# 4.net
KiCad netlist of a schematic drawn in Altium Designer
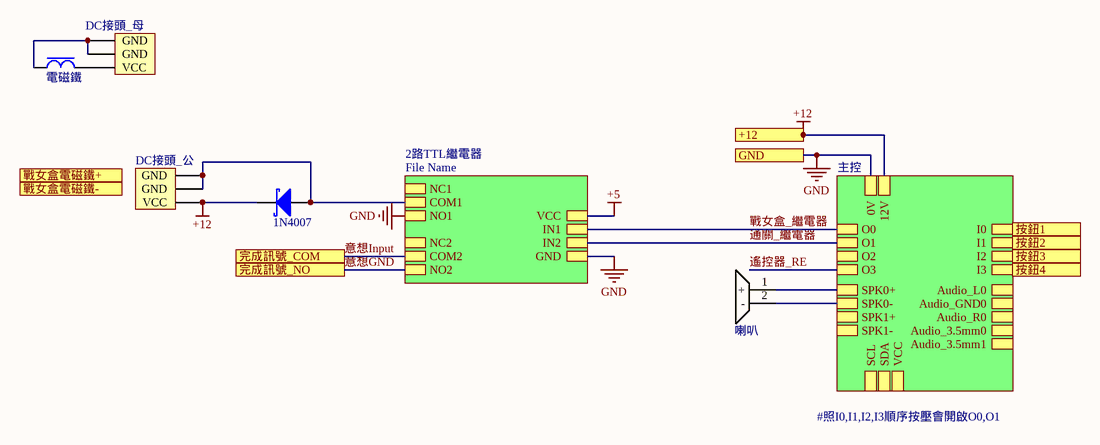
[diagram p0: 松菸_幻影光靈_屍禁_4順序按鈕.SchDoc]

(export (version "E")
  (design (tool "Eeschema 10.0.6"))
  (components
    (comp (ref "B38")
      (value "喇叭")
      (footprint "Buzzer_12085")
      (description "無源蜂鳴器")
      (libsource (lib "MyLibray") (part "Buzzer"))
    )
    (comp (ref "Cn94")
      (value "DC接頭_母")
      (footprint "Connector_DC-005")
      (description "連接器,DC直流接頭")
      (libsource (lib "") (part "Contact_DC_1"))
    )
    (comp (ref "Cn95")
      (value "DC接頭_公")
      (footprint "Connector_DC-005")
      (description "連接器,DC直流接頭")
      (libsource (lib "MyLibray") (part "Contact_DC"))
    )
    (comp (ref "I10")
      (value "電磁鐵")
      (footprint "Inductor-0420")
      (description "一體成型電感")
      (libsource (lib "MyLibray") (part "Inductor"))
    )
    (comp (ref "SD1")
      (value "1N4007")
      (footprint "Diode_SMA")
      (description "二極體_蕭特基")
      (libsource (lib "MyLibray") (part "Diode_Schottky"))
    )
  )
  (nets
    (net (code "2") (name "+12") (class "Default")
      (node (ref "Cn95") (pin "1") (pinfunction "VCC_1") (pintype "passive"))
      (node (ref "SD1") (pin "1") (pinfunction "K_1") (pintype "passive"))
    )
    (net (code "8") (name "/COM1") (class "Default")
      (node (ref "Cn95") (pin "2") (pinfunction "GND_2") (pintype "passive"))
      (node (ref "Cn95") (pin "3") (pinfunction "GND_3") (pintype "passive"))
      (node (ref "SD1") (pin "2") (pinfunction "A_2") (pintype "passive"))
    )
    (net (code "14") (name "/SPK0+") (class "Default")
      (node (ref "B38") (pin "1") (pinfunction "+_1") (pintype "passive"))
    )
    (net (code "15") (name "/SPK0-") (class "Default")
      (node (ref "B38") (pin "2") (pinfunction "-_2") (pintype "passive"))
    )
    (net (code "31") (name "Net-(Cn94-GND-Pad2)") (class "Default")
      (node (ref "Cn94") (pin "2") (pinfunction "GND_2") (pintype "passive"))
      (node (ref "Cn94") (pin "3") (pinfunction "GND_3") (pintype "passive"))
      (node (ref "I10") (pin "2") (pinfunction "2_2") (pintype "passive"))
    )
    (net (code "32") (name "Net-(Cn94-VCC)") (class "Default")
      (node (ref "Cn94") (pin "1") (pinfunction "VCC_1") (pintype "passive"))
      (node (ref "I10") (pin "1") (pinfunction "1_1") (pintype "passive"))
    )
  )
)
